# logger_2G_GSM.net
KiCad netlist of a schematic drawn in EAGLE
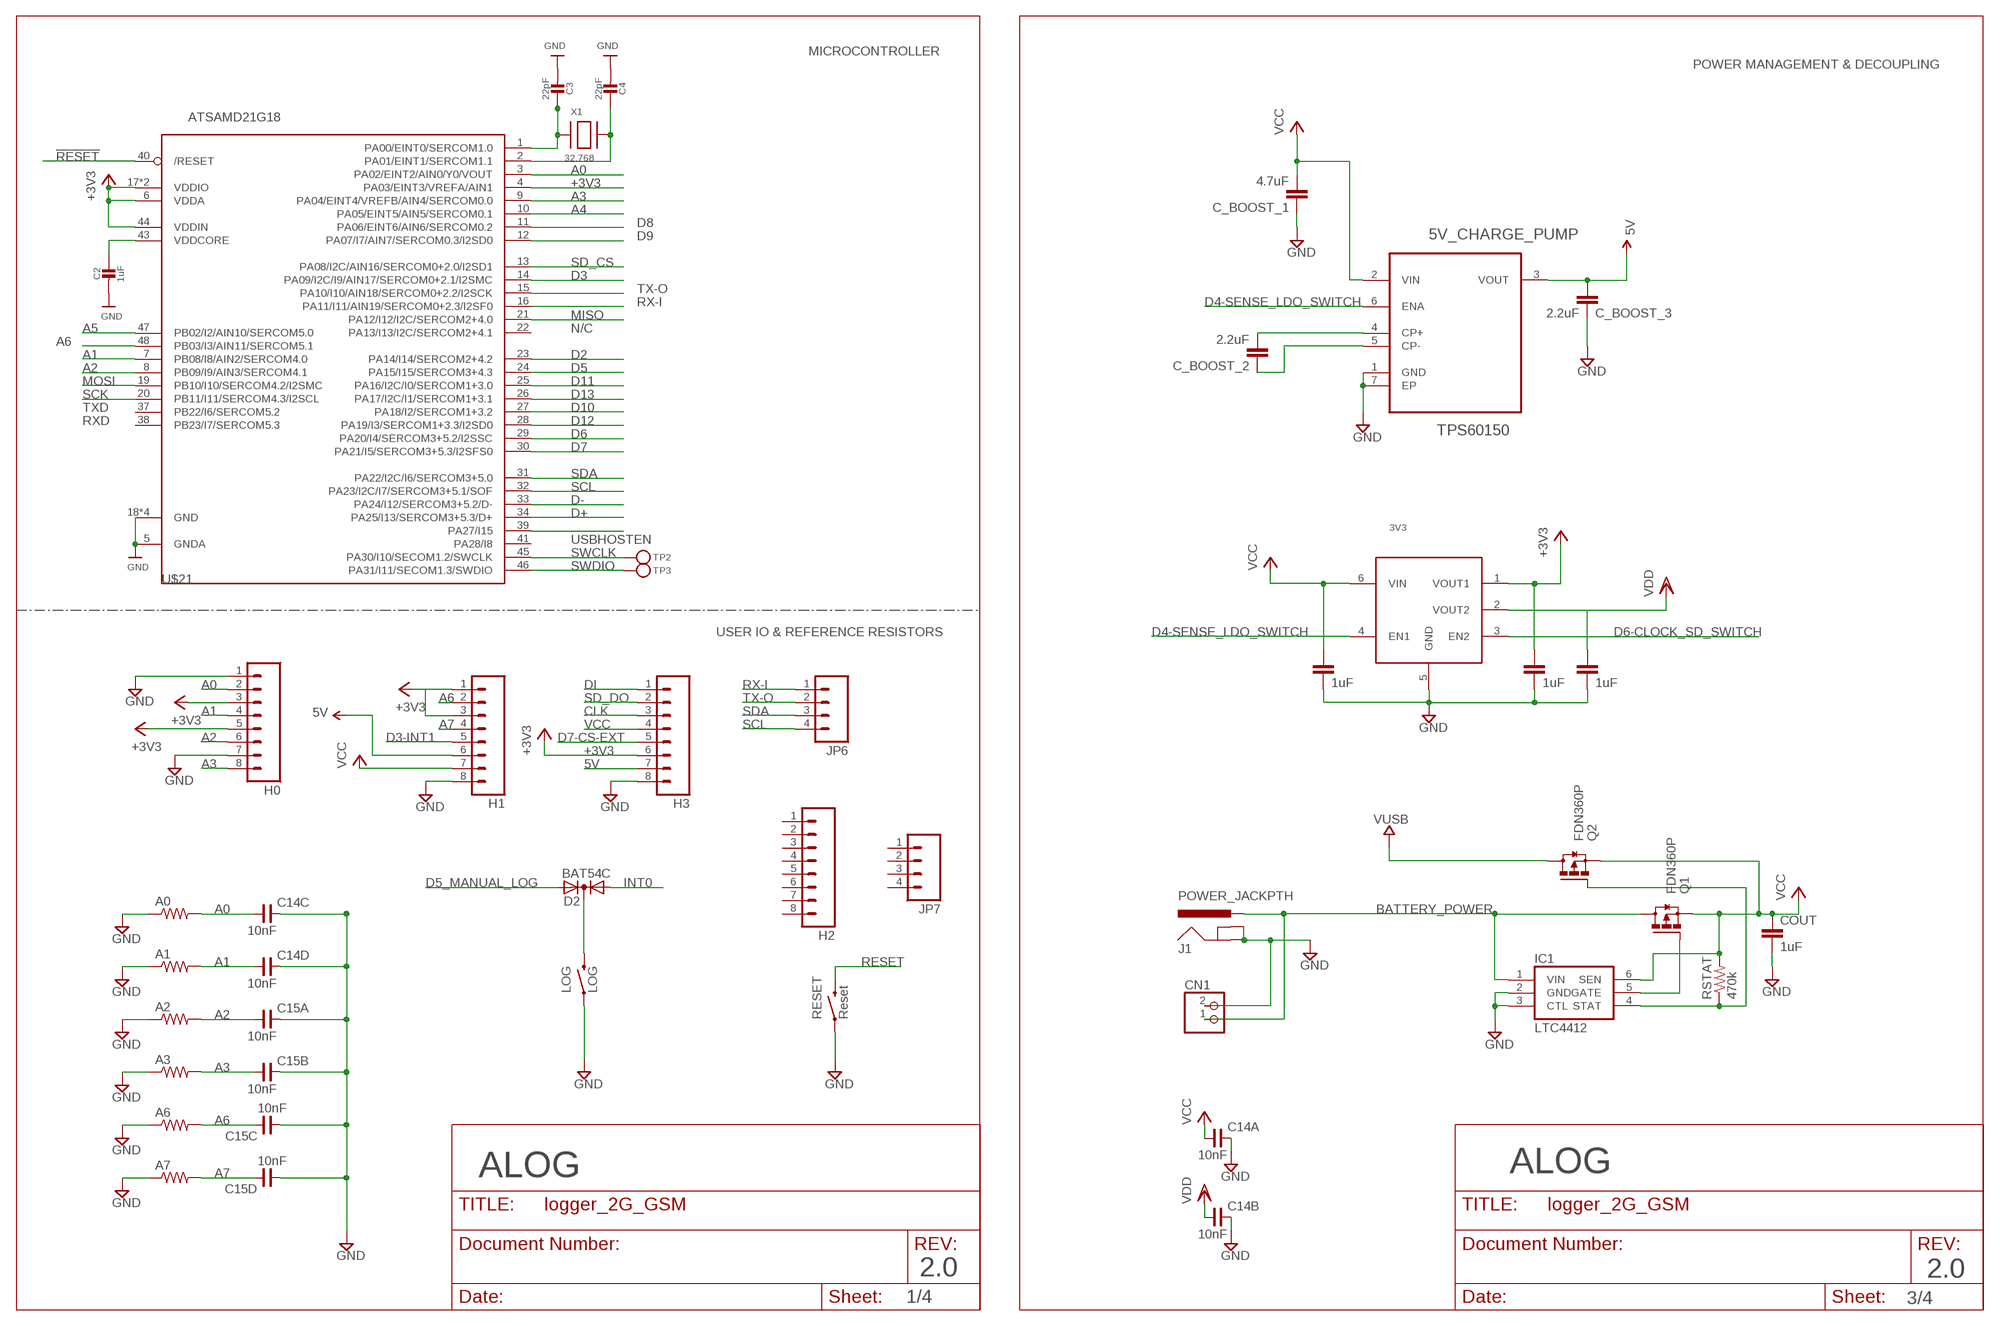
[diagram p0: schematic, sheet 1, part 1 of 2]
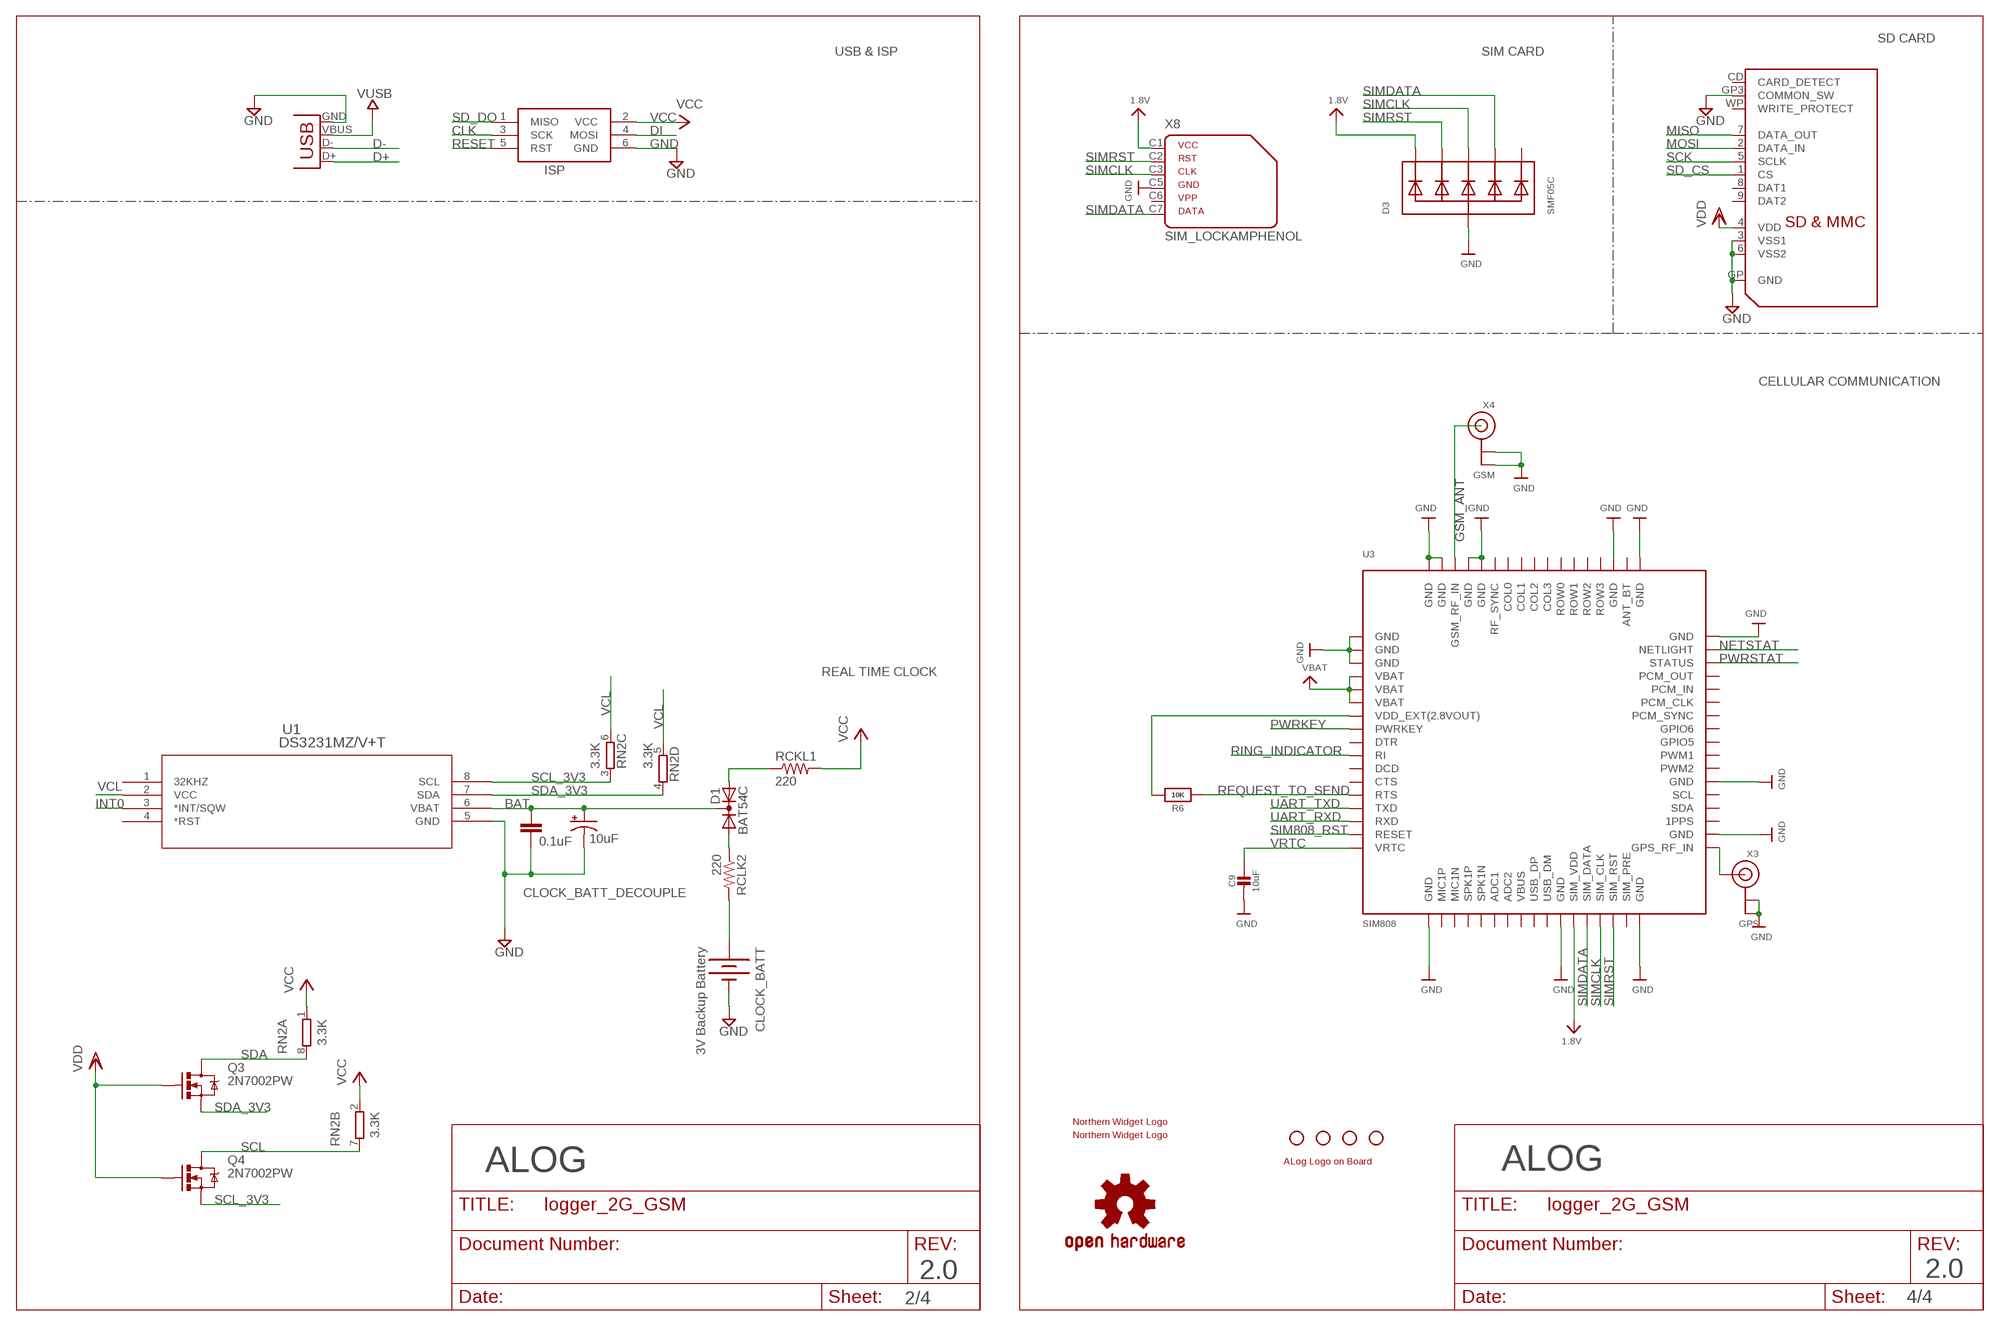
[diagram p1: schematic, sheet 1, part 2 of 2]

(export (version "E")
  (design (tool "Eeschema 10.0.6"))
  (components
    (comp (ref "3V3")
      (value "MIC5380")
      (footprint "eagle-import:6-TMLF")
      (libsource (lib "eagle-import") (part "MIC5380"))
    )
    (comp (ref "5V_CHARGE_PUMP")
      (value "TPS60150")
      (footprint "eagle-import:SON65P200X200X80-7N")
      (fields (field (name "MPN") "TPS60150DRVR"))
      (libsource (lib "eagle-import") (part "TPS60150DRVR"))
    )
    (comp (ref "A0")
      (value "R-US_0207/10")
      (footprint "eagle-import:0207_10")
      (libsource (lib "eagle-import") (part "resistor_R-US_0207/10"))
    )
    (comp (ref "A1")
      (value "R-US_0207/10")
      (footprint "eagle-import:0207_10")
      (libsource (lib "eagle-import") (part "resistor_R-US_0207/10"))
    )
    (comp (ref "A2")
      (value "R-US_0207/10")
      (footprint "eagle-import:0207_10")
      (libsource (lib "eagle-import") (part "resistor_R-US_0207/10"))
    )
    (comp (ref "A3")
      (value "R-US_0207/10")
      (footprint "eagle-import:0207_10")
      (libsource (lib "eagle-import") (part "resistor_R-US_0207/10"))
    )
    (comp (ref "A6")
      (value "R-US_0207/10")
      (footprint "eagle-import:0207_10")
      (libsource (lib "eagle-import") (part "resistor_R-US_0207/10"))
    )
    (comp (ref "A7")
      (value "R-US_0207/10")
      (footprint "eagle-import:0207_10")
      (libsource (lib "eagle-import") (part "resistor_R-US_0207/10"))
    )
    (comp (ref "C2")
      (value "1uF")
      (footprint "eagle-import:0603-NO")
      (libsource (lib "eagle-import") (part "CAP_CERAMIC0603_NO"))
    )
    (comp (ref "C3")
      (value "22pF")
      (footprint "eagle-import:0603-NO")
      (libsource (lib "eagle-import") (part "CAP_CERAMIC0603_NO"))
    )
    (comp (ref "C4")
      (value "22pF")
      (footprint "eagle-import:0603-NO")
      (libsource (lib "eagle-import") (part "CAP_CERAMIC0603_NO"))
    )
    (comp (ref "C9")
      (value "10uF")
      (footprint "eagle-import:0805-NO")
      (libsource (lib "eagle-import") (part "CAP_CERAMIC0805-NOOUTLINE"))
    )
    (comp (ref "C14")
      (value "10nF")
      (footprint "eagle-import:CECJ-1206")
      (libsource (lib "eagle-import") (part "CCA_ECJ-1206"))
    )
    (comp (ref "C15")
      (value "10nF")
      (footprint "eagle-import:CECJ-1206")
      (libsource (lib "eagle-import") (part "CCA_ECJ-1206"))
    )
    (comp (ref "CLOCK_BATT")
      (value "3V Backup Battery")
      (footprint "eagle-import:BATTCON_12MM_PTH")
      (libsource (lib "eagle-import") (part "BATTERY12PTH"))
    )
    (comp (ref "CLOCK_BATT_DECOUP")
      (value "0.1uF")
      (footprint "eagle-import:C0603")
      (libsource (lib "eagle-import") (part "C-EUC0603"))
    )
    (comp (ref "CLOCK_BATT_DECOUPLE")
      (value "10uF")
      (footprint "eagle-import:EIA3216")
      (libsource (lib "eagle-import") (part "CAP_POL1206"))
    )
    (comp (ref "CLOCK_CIN1")
      (value "1uF")
      (footprint "eagle-import:C0603")
      (libsource (lib "eagle-import") (part "C-EUC0603"))
    )
    (comp (ref "CLOCK_CIN2")
      (value "1uF")
      (footprint "eagle-import:C0603")
      (libsource (lib "eagle-import") (part "C-EUC0603"))
    )
    (comp (ref "CLOCK_CIN3")
      (value "1uF")
      (footprint "eagle-import:C0603")
      (libsource (lib "eagle-import") (part "C-EUC0603"))
    )
    (comp (ref "CN1")
      (value "JST_2PIN-THM")
      (footprint "eagle-import:JST-PH-2-THM")
      (libsource (lib "eagle-import") (part "JST_2PIN-THM"))
    )
    (comp (ref "COUT")
      (value "1uF")
      (footprint "eagle-import:C0603")
      (libsource (lib "eagle-import") (part "C-EUC0603"))
    )
    (comp (ref "C_BOOST_1")
      (value "4.7uF")
      (footprint "eagle-import:C0603")
      (libsource (lib "eagle-import") (part "resistor_C-EUC0603"))
    )
    (comp (ref "C_BOOST_2")
      (value "2.2uF")
      (footprint "eagle-import:C0603")
      (libsource (lib "eagle-import") (part "resistor_C-EUC0603"))
    )
    (comp (ref "C_BOOST_3")
      (value "2.2uF")
      (footprint "eagle-import:C0603")
      (libsource (lib "eagle-import") (part "resistor_C-EUC0603"))
    )
    (comp (ref "D1")
      (value "BAT54C")
      (footprint "eagle-import:SOT23C")
      (libsource (lib "eagle-import") (part "DIODE_AC-CA_"))
    )
    (comp (ref "D2")
      (value "BAT54C")
      (footprint "eagle-import:SOT23C")
      (libsource (lib "eagle-import") (part "DIODE_AC-CA_"))
    )
    (comp (ref "D3")
      (value "SMF05C")
      (footprint "eagle-import:SOT363")
      (libsource (lib "eagle-import") (part "TVSARRAY_5LANE"))
    )
    (comp (ref "H0")
      (value "M083.5MM-8")
      (footprint "eagle-import:SCREWTERMINAL-3.5MM-8")
      (libsource (lib "eagle-import") (part "M083.5MM-8"))
    )
    (comp (ref "H1")
      (value "M083.5MM-8")
      (footprint "eagle-import:SCREWTERMINAL-3.5MM-8")
      (libsource (lib "eagle-import") (part "M083.5MM-8"))
    )
    (comp (ref "H2")
      (value "M083.5MM-8")
      (footprint "eagle-import:SCREWTERMINAL-3.5MM-8")
      (libsource (lib "eagle-import") (part "M083.5MM-8"))
    )
    (comp (ref "H3")
      (value "M083.5MM-8")
      (footprint "eagle-import:SCREWTERMINAL-3.5MM-8")
      (libsource (lib "eagle-import") (part "M083.5MM-8"))
    )
    (comp (ref "IC1")
      (value "LTC4412")
      (footprint "eagle-import:TSOT23-6")
      (libsource (lib "eagle-import") (part "LTC4412S6E"))
    )
    (comp (ref "ISP")
      (value "AVRISP-6")
      (footprint "eagle-import:AVRISP")
      (libsource (lib "eagle-import") (part "AVRISP-6"))
    )
    (comp (ref "J1")
      (value "POWER_JACKPTH")
      (footprint "eagle-import:POWER_JACK_PTH")
      (libsource (lib "eagle-import") (part "POWER_JACKPTH"))
    )
    (comp (ref "JP1")
      (value "STAND-OFF")
      (footprint "eagle-import:STAND-OFF")
      (libsource (lib "eagle-import") (part "STAND-OFF"))
    )
    (comp (ref "JP2")
      (value "STAND-OFF")
      (footprint "eagle-import:STAND-OFF")
      (libsource (lib "eagle-import") (part "STAND-OFF"))
    )
    (comp (ref "JP3")
      (value "STAND-OFF")
      (footprint "eagle-import:STAND-OFF")
      (libsource (lib "eagle-import") (part "STAND-OFF"))
    )
    (comp (ref "JP4")
      (value "STAND-OFF")
      (footprint "eagle-import:STAND-OFF")
      (libsource (lib "eagle-import") (part "STAND-OFF"))
    )
    (comp (ref "JP5")
      (value "USB-B")
      (footprint "eagle-import:USB-B-PTH")
      (libsource (lib "eagle-import") (part "USBPTH"))
    )
    (comp (ref "JP6")
      (value "M04SCREW")
      (footprint "eagle-import:SCREWTERMINAL-3.5MM-4")
      (libsource (lib "eagle-import") (part "M04SCREW"))
    )
    (comp (ref "JP7")
      (value "M04SCREW")
      (footprint "eagle-import:SCREWTERMINAL-3.5MM-4")
      (libsource (lib "eagle-import") (part "M04SCREW"))
    )
    (comp (ref "LOG")
      (value "LOG")
      (footprint "eagle-import:TACTILE-PTH")
      (libsource (lib "eagle-import") (part "SWITCH-MOMENTARY-2PTH"))
    )
    (comp (ref "LOGO1")
      (value "OSHW-LOGOM")
      (footprint "eagle-import:OSHW-LOGO-M")
      (libsource (lib "eagle-import") (part "OSHW-LOGOM"))
    )
    (comp (ref "Q1")
      (value "FDN360P")
      (footprint "eagle-import:SUPER-SOT3")
      (libsource (lib "eagle-import") (part "FDN360P"))
    )
    (comp (ref "Q2")
      (value "FDN360P")
      (footprint "eagle-import:SUPER-SOT3")
      (libsource (lib "eagle-import") (part "FDN360P"))
    )
    (comp (ref "Q3")
      (value "2N7002PW")
      (footprint "eagle-import:SOT323")
      (libsource (lib "eagle-import") (part "MOSFET-NCHANNELSOT323"))
    )
    (comp (ref "Q4")
      (value "2N7002PW")
      (footprint "eagle-import:SOT323")
      (libsource (lib "eagle-import") (part "MOSFET-NCHANNELSOT323"))
    )
    (comp (ref "R6")
      (value "10K")
      (footprint "eagle-import:0805-NO")
      (libsource (lib "eagle-import") (part "RESISTOR0805_NOOUTLINE"))
    )
    (comp (ref "RCKL1")
      (value "220")
      (footprint "eagle-import:R0603")
      (libsource (lib "eagle-import") (part "R-US_R0603"))
    )
    (comp (ref "RCLK2")
      (value "220")
      (footprint "eagle-import:R0603")
      (libsource (lib "eagle-import") (part "R-US_R0603"))
    )
    (comp (ref "RESET")
      (value "Reset")
      (footprint "eagle-import:TACTILE-PTH")
      (libsource (lib "eagle-import") (part "SWITCH-MOMENTARY-2PTH"))
    )
    (comp (ref "RN2")
      (value "3.3K")
      (footprint "eagle-import:0603-ARC")
      (libsource (lib "eagle-import") (part "4R-N0603-ARC"))
    )
    (comp (ref "RSTAT")
      (value "470k")
      (footprint "eagle-import:R0603")
      (libsource (lib "eagle-import") (part "R-US_R0603"))
    )
    (comp (ref "SD")
      (value "SDMMC06132")
      (footprint "eagle-import:06132")
      (libsource (lib "eagle-import") (part "SDMMC06132"))
    )
    (comp (ref "TP2")
      (value "TESTPOINTROUND1.5MM")
      (footprint "eagle-import:TESTPOINT_ROUND_1.5MM")
      (libsource (lib "eagle-import") (part "TESTPOINTROUND1.5MM"))
    )
    (comp (ref "TP3")
      (value "TESTPOINTROUND1.5MM")
      (footprint "eagle-import:TESTPOINT_ROUND_1.5MM")
      (libsource (lib "eagle-import") (part "TESTPOINTROUND1.5MM"))
    )
    (comp (ref "U$1")
      (value "NWLOGO")
      (footprint "eagle-import:NWLOGO")
      (libsource (lib "eagle-import") (part "NWLOGO"))
    )
    (comp (ref "U$2")
      (value "ALOG_LOGO_V1_5.5MM")
      (footprint "eagle-import:ALOG_LOGO_V1_SMALL")
      (libsource (lib "eagle-import") (part "ALOG_LOGO_V1_5.5MM"))
    )
    (comp (ref "U$3")
      (value "NWLOGO_MED")
      (footprint "eagle-import:NWLOGO_MED")
      (libsource (lib "eagle-import") (part "NWLOGO_MED"))
    )
    (comp (ref "U$21")
      (value "ATSAMD21G18")
      (footprint "eagle-import:TQFN48_7MM")
      (libsource (lib "eagle-import") (part "ATSAMD21J_QFN"))
    )
    (comp (ref "U1")
      (value "DS3231MZ/V+T")
      (footprint "eagle-import:21-0041B_8")
      (libsource (lib "eagle-import") (part "DS3231MZ/V+T"))
    )
    (comp (ref "U3")
      (value "SIM808")
      (footprint "eagle-import:SIM900_SMT")
      (libsource (lib "eagle-import") (part "GSM_SIM808_LITERAL"))
    )
    (comp (ref "X1")
      (value "32.768")
      (footprint "eagle-import:XTAL3215")
      (libsource (lib "eagle-import") (part "XTAL-3.2X1.5"))
    )
    (comp (ref "X3")
      (value "GPS")
      (footprint "eagle-import:U.FL")
      (libsource (lib "eagle-import") (part "ANTENNA_U.FL"))
    )
    (comp (ref "X4")
      (value "GSM")
      (footprint "eagle-import:U.FL")
      (libsource (lib "eagle-import") (part "ANTENNA_U.FL"))
    )
    (comp (ref "X8")
      (value "SIM_LOCKAMPHENOL")
      (footprint "eagle-import:C707_10M006_512_2")
      (libsource (lib "eagle-import") (part "SIM_LOCKAMPHENOL"))
    )
  )
  (nets
    (net (code "1") (name "+3V3") (class "Default")
      (node (ref "3V3") (pin "1") (pinfunction "VOUT1_1") (pintype "power_in"))
      (node (ref "CLOCK_CIN2") (pin "1") (pinfunction "1_1") (pintype "passive"))
      (node (ref "H0") (pin "3") (pinfunction "3_3") (pintype "passive"))
      (node (ref "H0") (pin "5") (pinfunction "5_5") (pintype "passive"))
      (node (ref "H1") (pin "1") (pinfunction "1_1") (pintype "passive"))
      (node (ref "H1") (pin "3") (pinfunction "3_3") (pintype "passive"))
      (node (ref "H3") (pin "6") (pinfunction "6_6") (pintype "passive"))
      (node (ref "U$21") (pin "17") (pinfunction "VDDIO_17") (pintype "power_in"))
      (node (ref "U$21") (pin "36") (pinfunction "VDDIO_36") (pintype "power_in"))
      (node (ref "U$21") (pin "4") (pinfunction "PA03/EINT3/VREFA/AIN1_4") (pintype "bidirectional"))
      (node (ref "U$21") (pin "44") (pinfunction "VDDIN_44") (pintype "power_in"))
      (node (ref "U$21") (pin "6") (pinfunction "VDDA_6") (pintype "power_in"))
    )
    (net (code "2") (name "/A0") (class "Default")
      (node (ref "A0") (pin "2") (pinfunction "2_2") (pintype "passive"))
      (node (ref "C14") (pin "C1") (pinfunction "1_C1") (pintype "passive"))
      (node (ref "H0") (pin "2") (pinfunction "2_2") (pintype "passive"))
      (node (ref "U$21") (pin "3") (pinfunction "PA02/EINT2/AIN0/Y0/VOUT_3") (pintype "bidirectional"))
    )
    (net (code "3") (name "/A1") (class "Default")
      (node (ref "A1") (pin "2") (pinfunction "2_2") (pintype "passive"))
      (node (ref "C14") (pin "D1") (pinfunction "1_D1") (pintype "passive"))
      (node (ref "H0") (pin "4") (pinfunction "4_4") (pintype "passive"))
      (node (ref "U$21") (pin "7") (pinfunction "PB08/I8/AIN2/SERCOM4.0_7") (pintype "bidirectional"))
    )
    (net (code "4") (name "/A2") (class "Default")
      (node (ref "A2") (pin "2") (pinfunction "2_2") (pintype "passive"))
      (node (ref "C15") (pin "A1") (pinfunction "1_A1") (pintype "passive"))
      (node (ref "H0") (pin "6") (pinfunction "6_6") (pintype "passive"))
      (node (ref "U$21") (pin "8") (pinfunction "PB09/I9/AIN3/SERCOM4.1_8") (pintype "bidirectional"))
    )
    (net (code "5") (name "/A3") (class "Default")
      (node (ref "A3") (pin "2") (pinfunction "2_2") (pintype "passive"))
      (node (ref "C15") (pin "B1") (pinfunction "1_B1") (pintype "passive"))
      (node (ref "H0") (pin "8") (pinfunction "8_8") (pintype "passive"))
      (node (ref "U$21") (pin "9") (pinfunction "PA04/EINT4/VREFB/AIN4/SERCOM0.0_9") (pintype "bidirectional"))
    )
    (net (code "6") (name "/A4") (class "Default")
      (node (ref "U$21") (pin "10") (pinfunction "PA05/EINT5/AIN5/SERCOM0.1_10") (pintype "bidirectional"))
    )
    (net (code "7") (name "/A5") (class "Default")
      (node (ref "U$21") (pin "47") (pinfunction "PB02/I2/AIN10/SERCOM5.0_47") (pintype "bidirectional"))
    )
    (net (code "8") (name "/A6") (class "Default")
      (node (ref "A6") (pin "2") (pinfunction "2_2") (pintype "passive"))
      (node (ref "C15") (pin "C2") (pinfunction "2_C2") (pintype "passive"))
      (node (ref "H1") (pin "2") (pinfunction "2_2") (pintype "passive"))
      (node (ref "U$21") (pin "48") (pinfunction "PB03/I3/AIN11/SERCOM5.1_48") (pintype "bidirectional"))
    )
    (net (code "9") (name "/A7") (class "Default")
      (node (ref "A7") (pin "2") (pinfunction "2_2") (pintype "passive"))
      (node (ref "C15") (pin "D2") (pinfunction "2_D2") (pintype "passive"))
      (node (ref "H1") (pin "4") (pinfunction "4_4") (pintype "passive"))
    )
    (net (code "10") (name "/BAT") (class "Default")
      (node (ref "CLOCK_BATT_DECOUP") (pin "1") (pinfunction "1_1") (pintype "passive"))
      (node (ref "CLOCK_BATT_DECOUPLE") (pin "A") (pinfunction "+_A") (pintype "passive"))
      (node (ref "D1") (pin "3") (pinfunction "K_3") (pintype "passive"))
      (node (ref "U1") (pin "6") (pinfunction "VBAT_6") (pintype "power_in"))
    )
    (net (code "11") (name "/BATTERY_POWER") (class "Default")
      (node (ref "CN1") (pin "1") (pinfunction "2_1") (pintype "passive"))
      (node (ref "IC1") (pin "1") (pinfunction "VIN_1") (pintype "input"))
      (node (ref "J1") (pin "PWR") (pinfunction "PWR_PWR") (pintype "bidirectional"))
      (node (ref "Q1") (pin "3") (pinfunction "D_3") (pintype "passive"))
    )
    (net (code "12") (name "/CLK") (class "Default")
      (node (ref "H3") (pin "3") (pinfunction "3_3") (pintype "passive"))
      (node (ref "ISP") (pin "3") (pinfunction "SCK_3") (pintype "output"))
    )
    (net (code "13") (name "/D+") (class "Default")
      (node (ref "JP5") (pin "D+") (pinfunction "D+_D+") (pintype "bidirectional"))
      (node (ref "U$21") (pin "34") (pinfunction "PA25/I13/SERCOM3+5.3/D+_34") (pintype "bidirectional"))
    )
    (net (code "14") (name "/D-") (class "Default")
      (node (ref "JP5") (pin "D-") (pinfunction "D-_D-") (pintype "bidirectional"))
      (node (ref "U$21") (pin "33") (pinfunction "PA24/I12/SERCOM3+5.2/D-_33") (pintype "bidirectional"))
    )
    (net (code "15") (name "/D2") (class "Default")
      (node (ref "U$21") (pin "23") (pinfunction "PA14/I14/SERCOM2+4.2_23") (pintype "bidirectional"))
    )
    (net (code "16") (name "/D3") (class "Default")
      (node (ref "U$21") (pin "14") (pinfunction "PA09/I2C/I9/AIN17/SERCOM0+2.1/I2SMC_14") (pintype "bidirectional"))
    )
    (net (code "17") (name "/D3-INT1") (class "Default")
      (node (ref "H1") (pin "5") (pinfunction "5_5") (pintype "passive"))
    )
    (net (code "18") (name "/D4-SENSE_LDO_SWITCH") (class "Default")
      (node (ref "3V3") (pin "4") (pinfunction "EN1_4") (pintype "input"))
      (node (ref "5V_CHARGE_PUMP") (pin "6") (pinfunction "ENA_6") (pintype "input"))
    )
    (net (code "19") (name "/D5") (class "Default")
      (node (ref "U$21") (pin "24") (pinfunction "PA15/I15/SERCOM3+4.3_24") (pintype "bidirectional"))
    )
    (net (code "20") (name "/D5_MANUAL_LOG") (class "Default")
      (node (ref "D2") (pin "2") (pinfunction "A2_2") (pintype "passive"))
    )
    (net (code "21") (name "/D6") (class "Default")
      (node (ref "U$21") (pin "29") (pinfunction "PA20/I4/SERCOM3+5.2/I2SSC_29") (pintype "bidirectional"))
    )
    (net (code "22") (name "/D6-CLOCK_SD_SWITCH") (class "Default")
      (node (ref "3V3") (pin "3") (pinfunction "EN2_3") (pintype "input"))
    )
    (net (code "23") (name "/D7") (class "Default")
      (node (ref "U$21") (pin "30") (pinfunction "PA21/I5/SERCOM3+5.3/I2SFS0_30") (pintype "bidirectional"))
    )
    (net (code "24") (name "/D7-CS-EXT") (class "Default")
      (node (ref "H3") (pin "5") (pinfunction "5_5") (pintype "passive"))
    )
    (net (code "25") (name "/D8") (class "Default")
      (node (ref "U$21") (pin "11") (pinfunction "PA06/EINT6/AIN6/SERCOM0.2_11") (pintype "bidirectional"))
    )
    (net (code "26") (name "/D9") (class "Default")
      (node (ref "U$21") (pin "12") (pinfunction "PA07/I7/AIN7/SERCOM0.3/I2SD0_12") (pintype "bidirectional"))
    )
    (net (code "27") (name "/D10") (class "Default")
      (node (ref "U$21") (pin "27") (pinfunction "PA18/I2/SERCOM1+3.2_27") (pintype "bidirectional"))
    )
    (net (code "28") (name "/D11") (class "Default")
      (node (ref "U$21") (pin "25") (pinfunction "PA16/I2C/I0/SERCOM1+3.0_25") (pintype "bidirectional"))
    )
    (net (code "29") (name "/D12") (class "Default")
      (node (ref "U$21") (pin "28") (pinfunction "PA19/I3/SERCOM1+3.3/I2SD0_28") (pintype "bidirectional"))
    )
    (net (code "30") (name "/D13") (class "Default")
      (node (ref "U$21") (pin "26") (pinfunction "PA17/I2C/I1/SERCOM1+3.1_26") (pintype "bidirectional"))
    )
    (net (code "31") (name "/DI") (class "Default")
      (node (ref "H3") (pin "1") (pinfunction "1_1") (pintype "passive"))
      (node (ref "ISP") (pin "4") (pinfunction "MOSI_4") (pintype "output"))
    )
    (net (code "32") (name "/GSM_ANT") (class "Default")
      (node (ref "U3") (pin "P$66") (pinfunction "GSM_RF_IN_P$66") (pintype "input"))
      (node (ref "X4") (pin "3") (pinfunction "SIGNAL_3") (pintype "passive"))
    )
    (net (code "33") (name "/INT0") (class "Default")
      (node (ref "D2") (pin "1") (pinfunction "A1_1") (pintype "passive"))
      (node (ref "U1") (pin "3") (pinfunction "*INT/SQW_3") (pintype "passive"))
    )
    (net (code "34") (name "/MISO") (class "Default")
      (node (ref "SD") (pin "7") (pinfunction "DATA_OUT_7") (pintype "output"))
      (node (ref "U$21") (pin "21") (pinfunction "PA12/I12/I2C/SERCOM2+4.0_21") (pintype "bidirectional"))
    )
    (net (code "35") (name "/MOSI") (class "Default")
      (node (ref "SD") (pin "2") (pinfunction "DATA_IN_2") (pintype "input"))
      (node (ref "U$21") (pin "19") (pinfunction "PB10/I10/SERCOM4.2/I2SMC_19") (pintype "bidirectional"))
    )
    (net (code "36") (name "/NETSTAT") (class "Default")
      (node (ref "U3") (pin "P$50") (pinfunction "NETLIGHT_P$50") (pintype "output"))
    )
    (net (code "37") (name "/PWRKEY") (class "Default")
      (node (ref "U3") (pin "P$8") (pinfunction "PWRKEY_P$8") (pintype "input"))
    )
    (net (code "38") (name "/PWRSTAT") (class "Default")
      (node (ref "U3") (pin "P$49") (pinfunction "STATUS_P$49") (pintype "output"))
    )
    (net (code "39") (name "/REQUEST_TO_SEND") (class "Default")
      (node (ref "R6") (pin "1") (pinfunction "1_1") (pintype "passive"))
      (node (ref "U3") (pin "P$13") (pinfunction "RTS_P$13") (pintype "input"))
    )
    (net (code "40") (name "/RESET") (class "Default")
      (node (ref "ISP") (pin "5") (pinfunction "RST_5") (pintype "output"))
      (node (ref "RESET") (pin "3") (pinfunction "2_3") (pintype "passive"))
    )
    (net (code "41") (name "/RING_INDICATOR") (class "Default")
      (node (ref "U3") (pin "P$10") (pinfunction "RI_P$10") (pintype "output"))
    )
    (net (code "42") (name "/RX-I") (class "Default")
      (node (ref "JP6") (pin "1") (pinfunction "1_1") (pintype "passive"))
      (node (ref "U$21") (pin "16") (pinfunction "PA11/I11/AIN19/SERCOM0+2.3/I2SF0_16") (pintype "bidirectional"))
    )
    (net (code "43") (name "/SCK") (class "Default")
      (node (ref "SD") (pin "5") (pinfunction "SCLK_5") (pintype "input"))
      (node (ref "U$21") (pin "20") (pinfunction "PB11/I11/SERCOM4.3/I2SCL_20") (pintype "bidirectional"))
    )
    (net (code "44") (name "/SCL") (class "Default")
      (node (ref "JP6") (pin "4") (pinfunction "4_4") (pintype "passive"))
      (node (ref "Q4") (pin "3") (pinfunction "D_3") (pintype "passive"))
      (node (ref "RN2") (pin "7") (pinfunction "2_7") (pintype "passive"))
      (node (ref "U$21") (pin "32") (pinfunction "PA23/I2C/I7/SERCOM3+5.1/SOF_32") (pintype "bidirectional"))
    )
    (net (code "45") (name "/SCL_3V3") (class "Default")
      (node (ref "Q4") (pin "2") (pinfunction "S_2") (pintype "passive"))
      (node (ref "RN2") (pin "3") (pinfunction "1_3") (pintype "passive"))
      (node (ref "U1") (pin "8") (pinfunction "SCL_8") (pintype "passive"))
    )
    (net (code "46") (name "/SDA") (class "Default")
      (node (ref "JP6") (pin "3") (pinfunction "3_3") (pintype "passive"))
      (node (ref "Q3") (pin "3") (pinfunction "D_3") (pintype "passive"))
      (node (ref "RN2") (pin "8") (pinfunction "2_8") (pintype "passive"))
      (node (ref "U$21") (pin "31") (pinfunction "PA22/I2C/I6/SERCOM3+5.0_31") (pintype "bidirectional"))
    )
    (net (code "47") (name "/SDA_3V3") (class "Default")
      (node (ref "Q3") (pin "2") (pinfunction "S_2") (pintype "passive"))
      (node (ref "RN2") (pin "4") (pinfunction "1_4") (pintype "passive"))
      (node (ref "U1") (pin "7") (pinfunction "SDA_7") (pintype "passive"))
    )
    (net (code "48") (name "/SD_CS") (class "Default")
      (node (ref "SD") (pin "1") (pinfunction "CS_1") (pintype "input"))
      (node (ref "U$21") (pin "13") (pinfunction "PA08/I2C/AIN16/SERCOM0+2.0/I2SD1_13") (pintype "bidirectional"))
    )
    (net (code "49") (name "/SD_DO") (class "Default")
      (node (ref "H3") (pin "2") (pinfunction "2_2") (pintype "passive"))
      (node (ref "ISP") (pin "1") (pinfunction "MISO_1") (pintype "input"))
    )
    (net (code "50") (name "/SIM808_RST") (class "Default")
      (node (ref "U3") (pin "P$16") (pinfunction "RESET_P$16") (pintype "input"))
    )
    (net (code "51") (name "/SIMCLK") (class "Default")
      (node (ref "D3") (pin "4") (pinfunction "C3_4") (pintype "passive"))
      (node (ref "U3") (pin "P$31") (pinfunction "SIM_CLK_P$31") (pintype "output"))
      (node (ref "X8") (pin "C3") (pinfunction "3_C3") (pintype "passive"))
    )
    (net (code "52") (name "/SIMDATA") (class "Default")
      (node (ref "D3") (pin "5") (pinfunction "C4_5") (pintype "passive"))
      (node (ref "U3") (pin "P$30") (pinfunction "SIM_DATA_P$30") (pintype "bidirectional"))
      (node (ref "X8") (pin "C7") (pinfunction "6_C7") (pintype "passive"))
    )
    (net (code "53") (name "/SIMRST") (class "Default")
      (node (ref "D3") (pin "3") (pinfunction "C2_3") (pintype "passive"))
      (node (ref "U3") (pin "P$32") (pinfunction "SIM_RST_P$32") (pintype "output"))
      (node (ref "X8") (pin "C2") (pinfunction "2_C2") (pintype "passive"))
    )
    (net (code "54") (name "/SWCLK") (class "Default")
      (node (ref "TP2") (pin "P$1") (pinfunction "P$1_P$1") (pintype "bidirectional"))
      (node (ref "U$21") (pin "45") (pinfunction "PA30/I10/SECOM1.2/SWCLK_45") (pintype "bidirectional"))
    )
    (net (code "55") (name "/SWDIO") (class "Default")
      (node (ref "TP3") (pin "P$1") (pinfunction "P$1_P$1") (pintype "bidirectional"))
      (node (ref "U$21") (pin "46") (pinfunction "PA31/I11/SECOM1.3/SWDIO_46") (pintype "bidirectional"))
    )
    (net (code "56") (name "/TX-O") (class "Default")
      (node (ref "JP6") (pin "2") (pinfunction "2_2") (pintype "passive"))
      (node (ref "U$21") (pin "15") (pinfunction "PA10/I10/AIN18/SERCOM0+2.2/I2SCK_15") (pintype "bidirectional"))
    )
    (net (code "57") (name "/UART_RXD") (class "Default")
      (node (ref "U3") (pin "P$15") (pinfunction "RXD_P$15") (pintype "input"))
    )
    (net (code "58") (name "/UART_TXD") (class "Default")
      (node (ref "U3") (pin "P$14") (pinfunction "TXD_P$14") (pintype "output"))
    )
    (net (code "59") (name "/VBUS") (class "Default")
      (node (ref "U3") (pin "P$25") (pinfunction "VBUS_P$25") (pintype "power_in"))
    )
    (net (code "60") (name "/VCL") (class "Default")
      (node (ref "RN2") (pin "5") (pinfunction "2_5") (pintype "passive"))
      (node (ref "RN2") (pin "6") (pinfunction "2_6") (pintype "passive"))
      (node (ref "U1") (pin "2") (pinfunction "VCC_2") (pintype "power_in"))
    )
    (net (code "61") (name "/VRTC") (class "Default")
      (node (ref "C9") (pin "1") (pinfunction "1_1") (pintype "passive"))
      (node (ref "U3") (pin "P$17") (pinfunction "VRTC_P$17") (pintype "power_in"))
    )
    (net (code "62") (name "/~{RESET}") (class "Default")
      (node (ref "U$21") (pin "40") (pinfunction "/RESET_40") (pintype "bidirectional"))
    )
    (net (code "63") (name "1.8V") (class "Default")
      (node (ref "D3") (pin "1") (pinfunction "C1_1") (pintype "passive"))
      (node (ref "U3") (pin "P$29") (pinfunction "SIM_VDD_P$29") (pintype "power_in"))
      (node (ref "X8") (pin "C1") (pinfunction "1_C1") (pintype "passive"))
    )
    (net (code "64") (name "5V") (class "Default")
      (node (ref "5V_CHARGE_PUMP") (pin "3") (pinfunction "VOUT_3") (pintype "output"))
      (node (ref "C_BOOST_3") (pin "2") (pinfunction "2_2") (pintype "passive"))
      (node (ref "H1") (pin "6") (pinfunction "6_6") (pintype "passive"))
      (node (ref "H3") (pin "7") (pinfunction "7_7") (pintype "passive"))
    )
    (net (code "65") (name "GND") (class "Default")
      (node (ref "3V3") (pin "5") (pinfunction "GND_5") (pintype "power_in"))
      (node (ref "5V_CHARGE_PUMP") (pin "1") (pinfunction "GND_1") (pintype "passive"))
      (node (ref "5V_CHARGE_PUMP") (pin "7") (pinfunction "EP_7") (pintype "passive"))
      (node (ref "A0") (pin "1") (pinfunction "1_1") (pintype "passive"))
      (node (ref "A1") (pin "1") (pinfunction "1_1") (pintype "passive"))
      (node (ref "A2") (pin "1") (pinfunction "1_1") (pintype "passive"))
      (node (ref "A3") (pin "1") (pinfunction "1_1") (pintype "passive"))
      (node (ref "A6") (pin "1") (pinfunction "1_1") (pintype "passive"))
      (node (ref "A7") (pin "1") (pinfunction "1_1") (pintype "passive"))
      (node (ref "C14") (pin "A2") (pinfunction "2_A2") (pintype "passive"))
      (node (ref "C14") (pin "B2") (pinfunction "2_B2") (pintype "passive"))
      (node (ref "C14") (pin "C2") (pinfunction "2_C2") (pintype "passive"))
      (node (ref "C14") (pin "D2") (pinfunction "2_D2") (pintype "passive"))
      (node (ref "C15") (pin "A2") (pinfunction "2_A2") (pintype "passive"))
      (node (ref "C15") (pin "B2") (pinfunction "2_B2") (pintype "passive"))
      (node (ref "C15") (pin "C1") (pinfunction "1_C1") (pintype "passive"))
      (node (ref "C15") (pin "D1") (pinfunction "1_D1") (pintype "passive"))
      (node (ref "C2") (pin "2") (pinfunction "2_2") (pintype "passive"))
      (node (ref "C3") (pin "2") (pinfunction "2_2") (pintype "passive"))
      (node (ref "C4") (pin "2") (pinfunction "2_2") (pintype "passive"))
      (node (ref "C9") (pin "2") (pinfunction "2_2") (pintype "passive"))
      (node (ref "CLOCK_BATT") (pin "GND") (pinfunction "-_GND") (pintype "power_in"))
      (node (ref "CLOCK_BATT_DECOUP") (pin "2") (pinfunction "2_2") (pintype "passive"))
      (node (ref "CLOCK_BATT_DECOUPLE") (pin "C") (pinfunction "-_C") (pintype "passive"))
      (node (ref "CLOCK_CIN1") (pin "2") (pinfunction "2_2") (pintype "passive"))
      (node (ref "CLOCK_CIN2") (pin "2") (pinfunction "2_2") (pintype "passive"))
      (node (ref "CLOCK_CIN3") (pin "2") (pinfunction "2_2") (pintype "passive"))
      (node (ref "CN1") (pin "2") (pinfunction "1_2") (pintype "passive"))
      (node (ref "COUT") (pin "2") (pinfunction "2_2") (pintype "passive"))
      (node (ref "C_BOOST_1") (pin "1") (pinfunction "1_1") (pintype "passive"))
      (node (ref "C_BOOST_3") (pin "1") (pinfunction "1_1") (pintype "passive"))
      (node (ref "D3") (pin "2") (pinfunction "A_2") (pintype "passive"))
      (node (ref "H0") (pin "1") (pinfunction "1_1") (pintype "passive"))
      (node (ref "H0") (pin "7") (pinfunction "7_7") (pintype "passive"))
      (node (ref "H1") (pin "8") (pinfunction "8_8") (pintype "passive"))
      (node (ref "H3") (pin "8") (pinfunction "8_8") (pintype "passive"))
      (node (ref "IC1") (pin "2") (pinfunction "GND_2") (pintype "passive"))
      (node (ref "IC1") (pin "3") (pinfunction "CTL_3") (pintype "input"))
      (node (ref "ISP") (pin "6") (pinfunction "GND_6") (pintype "power_in"))
      (node (ref "J1") (pin "GND") (pinfunction "GND_GND") (pintype "bidirectional"))
      (node (ref "J1") (pin "GNDBREAK") (pinfunction "GNDBREAK_GNDBREAK") (pintype "bidirectional"))
      (node (ref "JP5") (pin "GND") (pinfunction "GND_GND") (pintype "bidirectional"))
      (node (ref "LOG") (pin "1") (pinfunction "1_1") (pintype "passive"))
      (node (ref "RESET") (pin "1") (pinfunction "1_1") (pintype "passive"))
      (node (ref "SD") (pin "3") (pinfunction "VSS1_3") (pintype "power_in"))
      (node (ref "SD") (pin "6") (pinfunction "VSS2_6") (pintype "power_in"))
      (node (ref "SD") (pin "GP") (pinfunction "GND_GP") (pintype "power_in"))
      (node (ref "SD") (pin "GP3") (pinfunction "COMMON_SW_GP3") (pintype "passive"))
      (node (ref "U$21") (pin "18") (pinfunction "GND_18") (pintype "power_in"))
      (node (ref "U$21") (pin "35") (pinfunction "GND_35") (pintype "power_in"))
      (node (ref "U$21") (pin "42") (pinfunction "GND_42") (pintype "power_in"))
      (node (ref "U$21") (pin "5") (pinfunction "GNDA_5") (pintype "power_in"))
      (node (ref "U$21") (pin "THERMAL") (pinfunction "GND_THERMAL") (pintype "power_in"))
      (node (ref "U1") (pin "5") (pinfunction "GND_5") (pintype "power_in"))
      (node (ref "U3") (pin "P$1") (pinfunction "GND_P$1") (pintype "power_in"))
      (node (ref "U3") (pin "P$18") (pinfunction "GND_P$18") (pintype "power_in"))
      (node (ref "U3") (pin "P$2") (pinfunction "GND_P$2") (pintype "power_in"))
      (node (ref "U3") (pin "P$28") (pinfunction "GND_P$28") (pintype "power_in"))
      (node (ref "U3") (pin "P$3") (pinfunction "GND_P$3") (pintype "power_in"))
      (node (ref "U3") (pin "P$34") (pinfunction "GND_P$34") (pintype "power_in"))
      (node (ref "U3") (pin "P$36") (pinfunction "GND_P$36") (pintype "power_in"))
      (node (ref "U3") (pin "P$40") (pinfunction "GND_P$40") (pintype "power_in"))
      (node (ref "U3") (pin "P$51") (pinfunction "GND_P$51") (pintype "power_in"))
      (node (ref "U3") (pin "P$52") (pinfunction "GND_P$52") (pintype "power_in"))
      (node (ref "U3") (pin "P$54") (pinfunction "GND_P$54") (pintype "power_in"))
      (node (ref "U3") (pin "P$64") (pinfunction "GND_P$64") (pintype "power_in"))
      (node (ref "U3") (pin "P$65") (pinfunction "GND_P$65") (pintype "power_in"))
      (node (ref "U3") (pin "P$67") (pinfunction "GND_P$67") (pintype "power_in"))
      (node (ref "U3") (pin "P$68") (pinfunction "GND_P$68") (pintype "power_in"))
      (node (ref "X3") (pin "1") (pinfunction "GND_1") (pintype "passive"))
      (node (ref "X3") (pin "2") (pinfunction "GND_2") (pintype "passive"))
      (node (ref "X4") (pin "1") (pinfunction "GND_1") (pintype "passive"))
      (node (ref "X4") (pin "2") (pinfunction "GND_2") (pintype "passive"))
      (node (ref "X8") (pin "C5") (pinfunction "4_C5") (pintype "passive"))
    )
    (net (code "66") (name "Net-(5V_CHARGE_PUMP-CP+)") (class "Default")
      (node (ref "5V_CHARGE_PUMP") (pin "4") (pinfunction "CP+_4") (pintype "passive"))
      (node (ref "C_BOOST_2") (pin "2") (pinfunction "2_2") (pintype "passive"))
    )
    (net (code "67") (name "Net-(5V_CHARGE_PUMP-CP-)") (class "Default")
      (node (ref "5V_CHARGE_PUMP") (pin "5") (pinfunction "CP-_5") (pintype "passive"))
      (node (ref "C_BOOST_2") (pin "1") (pinfunction "1_1") (pintype "passive"))
    )
    (net (code "68") (name "Net-(CLOCK_BATT-+)") (class "Default")
      (node (ref "CLOCK_BATT") (pin "VCC@1") (pinfunction "+_VCC@1") (pintype "power_in"))
      (node (ref "RCLK2") (pin "2") (pinfunction "2_2") (pintype "passive"))
    )
    (net (code "69") (name "Net-(D1-A1)") (class "Default")
      (node (ref "D1") (pin "1") (pinfunction "A1_1") (pintype "passive"))
      (node (ref "RCLK2") (pin "1") (pinfunction "1_1") (pintype "passive"))
    )
    (net (code "70") (name "Net-(D1-A2)") (class "Default")
      (node (ref "D1") (pin "2") (pinfunction "A2_2") (pintype "passive"))
      (node (ref "RCKL1") (pin "1") (pinfunction "1_1") (pintype "passive"))
    )
    (net (code "71") (name "Net-(D2-K)") (class "Default")
      (node (ref "D2") (pin "3") (pinfunction "K_3") (pintype "passive"))
      (node (ref "LOG") (pin "3") (pinfunction "2_3") (pintype "passive"))
    )
    (net (code "72") (name "Net-(IC1-GATE)") (class "Default")
      (node (ref "IC1") (pin "5") (pinfunction "GATE_5") (pintype "output"))
      (node (ref "Q1") (pin "1") (pinfunction "G_1") (pintype "passive"))
    )
    (net (code "73") (name "Net-(IC1-STAT)") (class "Default")
      (node (ref "IC1") (pin "4") (pinfunction "STAT_4") (pintype "open_collector"))
      (node (ref "Q2") (pin "1") (pinfunction "G_1") (pintype "passive"))
      (node (ref "RSTAT") (pin "1") (pinfunction "1_1") (pintype "passive"))
    )
    (net (code "74") (name "Net-(U$21-PA00{slash}EINT0{slash}SERCOM1.0)") (class "Default")
      (node (ref "C3") (pin "1") (pinfunction "1_1") (pintype "passive"))
      (node (ref "U$21") (pin "1") (pinfunction "PA00/EINT0/SERCOM1.0_1") (pintype "bidirectional"))
      (node (ref "X1") (pin "P$1") (pinfunction "P$1_P$1") (pintype "bidirectional"))
    )
    (net (code "75") (name "Net-(U$21-PA01{slash}EINT1{slash}SERCOM1.1)") (class "Default")
      (node (ref "C4") (pin "1") (pinfunction "1_1") (pintype "passive"))
      (node (ref "U$21") (pin "2") (pinfunction "PA01/EINT1/SERCOM1.1_2") (pintype "bidirectional"))
      (node (ref "X1") (pin "P$2") (pinfunction "P$2_P$2") (pintype "bidirectional"))
    )
    (net (code "76") (name "Net-(U$21-VDDCORE)") (class "Default")
      (node (ref "C2") (pin "1") (pinfunction "1_1") (pintype "passive"))
      (node (ref "U$21") (pin "43") (pinfunction "VDDCORE_43") (pintype "power_in"))
    )
    (net (code "77") (name "Net-(U3-GPS_RF_IN)") (class "Default")
      (node (ref "U3") (pin "P$35") (pinfunction "GPS_RF_IN_P$35") (pintype "bidirectional"))
      (node (ref "X3") (pin "3") (pinfunction "SIGNAL_3") (pintype "passive"))
    )
    (net (code "78") (name "Net-(U3-VDD_EXT(2.8VOUT))") (class "Default")
      (node (ref "R6") (pin "2") (pinfunction "2_2") (pintype "passive"))
      (node (ref "U3") (pin "P$7") (pinfunction "VDD_EXT(2.8VOUT)_P$7") (pintype "power_in"))
    )
    (net (code "79") (name "VBAT") (class "Default")
      (node (ref "U3") (pin "P$4") (pinfunction "VBAT_P$4") (pintype "power_in"))
      (node (ref "U3") (pin "P$5") (pinfunction "VBAT_P$5") (pintype "power_in"))
      (node (ref "U3") (pin "P$6") (pinfunction "VBAT_P$6") (pintype "power_in"))
    )
    (net (code "80") (name "VCC") (class "Default")
      (node (ref "3V3") (pin "6") (pinfunction "VIN_6") (pintype "power_in"))
      (node (ref "5V_CHARGE_PUMP") (pin "2") (pinfunction "VIN_2") (pintype "power_in"))
      (node (ref "C14") (pin "A1") (pinfunction "1_A1") (pintype "passive"))
      (node (ref "CLOCK_CIN1") (pin "1") (pinfunction "1_1") (pintype "passive"))
      (node (ref "COUT") (pin "1") (pinfunction "1_1") (pintype "passive"))
      (node (ref "C_BOOST_1") (pin "2") (pinfunction "2_2") (pintype "passive"))
      (node (ref "H1") (pin "7") (pinfunction "7_7") (pintype "passive"))
      (node (ref "H3") (pin "4") (pinfunction "4_4") (pintype "passive"))
      (node (ref "IC1") (pin "6") (pinfunction "SEN_6") (pintype "input"))
      (node (ref "ISP") (pin "2") (pinfunction "VCC_2") (pintype "power_in"))
      (node (ref "Q1") (pin "2") (pinfunction "S_2") (pintype "passive"))
      (node (ref "Q2") (pin "2") (pinfunction "S_2") (pintype "passive"))
      (node (ref "RCKL1") (pin "2") (pinfunction "2_2") (pintype "passive"))
      (node (ref "RN2") (pin "1") (pinfunction "1_1") (pintype "passive"))
      (node (ref "RN2") (pin "2") (pinfunction "1_2") (pintype "passive"))
      (node (ref "RSTAT") (pin "2") (pinfunction "2_2") (pintype "passive"))
    )
    (net (code "81") (name "VDD") (class "Default")
      (node (ref "3V3") (pin "2") (pinfunction "VOUT2_2") (pintype "power_in"))
      (node (ref "C14") (pin "B1") (pinfunction "1_B1") (pintype "passive"))
      (node (ref "CLOCK_CIN3") (pin "1") (pinfunction "1_1") (pintype "passive"))
      (node (ref "Q3") (pin "1") (pinfunction "G_1") (pintype "passive"))
      (node (ref "Q4") (pin "1") (pinfunction "G_1") (pintype "passive"))
      (node (ref "SD") (pin "4") (pinfunction "VDD_4") (pintype "power_in"))
    )
    (net (code "82") (name "VUSB") (class "Default")
      (node (ref "JP5") (pin "VBUS") (pinfunction "VBUS_VBUS") (pintype "bidirectional"))
      (node (ref "Q2") (pin "3") (pinfunction "D_3") (pintype "passive"))
    )
    (net (code "83") (name "unconnected-(D3-C5-Pad6)") (class "Default")
      (node (ref "D3") (pin "6") (pinfunction "C5_6") (pintype "passive"))
    )
    (net (code "84") (name "unconnected-(H2-Pad1)") (class "Default")
      (node (ref "H2") (pin "1") (pinfunction "1_1") (pintype "passive"))
    )
    (net (code "85") (name "unconnected-(H2-Pad2)") (class "Default")
      (node (ref "H2") (pin "2") (pinfunction "2_2") (pintype "passive"))
    )
    (net (code "86") (name "unconnected-(H2-Pad3)") (class "Default")
      (node (ref "H2") (pin "3") (pinfunction "3_3") (pintype "passive"))
    )
    (net (code "87") (name "unconnected-(H2-Pad4)") (class "Default")
      (node (ref "H2") (pin "4") (pinfunction "4_4") (pintype "passive"))
    )
    (net (code "88") (name "unconnected-(H2-Pad5)") (class "Default")
      (node (ref "H2") (pin "5") (pinfunction "5_5") (pintype "passive"))
    )
    (net (code "89") (name "unconnected-(H2-Pad6)") (class "Default")
      (node (ref "H2") (pin "6") (pinfunction "6_6") (pintype "passive"))
    )
    (net (code "90") (name "unconnected-(H2-Pad7)") (class "Default")
      (node (ref "H2") (pin "7") (pinfunction "7_7") (pintype "passive"))
    )
    (net (code "91") (name "unconnected-(H2-Pad8)") (class "Default")
      (node (ref "H2") (pin "8") (pinfunction "8_8") (pintype "passive"))
    )
    (net (code "92") (name "unconnected-(JP7-Pad1)") (class "Default")
      (node (ref "JP7") (pin "1") (pinfunction "1_1") (pintype "passive"))
    )
    (net (code "93") (name "unconnected-(JP7-Pad2)") (class "Default")
      (node (ref "JP7") (pin "2") (pinfunction "2_2") (pintype "passive"))
    )
    (net (code "94") (name "unconnected-(JP7-Pad3)") (class "Default")
      (node (ref "JP7") (pin "3") (pinfunction "3_3") (pintype "passive"))
    )
    (net (code "95") (name "unconnected-(JP7-Pad4)") (class "Default")
      (node (ref "JP7") (pin "4") (pinfunction "4_4") (pintype "passive"))
    )
    (net (code "96") (name "unconnected-(SD-CARD_DETECT-PadCD)") (class "Default")
      (node (ref "SD") (pin "CD") (pinfunction "CARD_DETECT_CD") (pintype "passive"))
    )
    (net (code "97") (name "unconnected-(SD-DAT1-Pad8)") (class "Default")
      (node (ref "SD") (pin "8") (pinfunction "DAT1_8") (pintype "bidirectional"))
    )
    (net (code "98") (name "unconnected-(SD-DAT2-Pad9)") (class "Default")
      (node (ref "SD") (pin "9") (pinfunction "DAT2_9") (pintype "bidirectional"))
    )
    (net (code "99") (name "unconnected-(SD-WRITE_PROTECT-PadWP)") (class "Default")
      (node (ref "SD") (pin "WP") (pinfunction "WRITE_PROTECT_WP") (pintype "passive"))
    )
    (net (code "100") (name "unconnected-(U$21-PA13{slash}I13{slash}I2C{slash}SERCOM2+4.1-Pad22)") (class "Default")
      (node (ref "U$21") (pin "22") (pinfunction "PA13/I13/I2C/SERCOM2+4.1_22") (pintype "bidirectional"))
    )
    (net (code "101") (name "unconnected-(U$21-PA27{slash}I15-Pad39)") (class "Default")
      (node (ref "U$21") (pin "39") (pinfunction "PA27/I15_39") (pintype "bidirectional"))
    )
    (net (code "102") (name "unconnected-(U$21-PA28{slash}I8-Pad41)") (class "Default")
      (node (ref "U$21") (pin "41") (pinfunction "PA28/I8_41") (pintype "bidirectional"))
    )
    (net (code "103") (name "unconnected-(U$21-PB22{slash}I6{slash}SERCOM5.2-Pad37)") (class "Default")
      (node (ref "U$21") (pin "37") (pinfunction "PB22/I6/SERCOM5.2_37") (pintype "bidirectional"))
    )
    (net (code "104") (name "unconnected-(U$21-PB23{slash}I7{slash}SERCOM5.3-Pad38)") (class "Default")
      (node (ref "U$21") (pin "38") (pinfunction "PB23/I7/SERCOM5.3_38") (pintype "bidirectional"))
    )
    (net (code "105") (name "unconnected-(U1-*RST-Pad4)") (class "Default")
      (node (ref "U1") (pin "4") (pinfunction "*RST_4") (pintype "passive"))
    )
    (net (code "106") (name "unconnected-(U1-32KHZ-Pad1)") (class "Default")
      (node (ref "U1") (pin "1") (pinfunction "32KHZ_1") (pintype "passive"))
    )
    (net (code "107") (name "unconnected-(U3-1PPS-PadP$37)") (class "Default")
      (node (ref "U3") (pin "P$37") (pinfunction "1PPS_P$37") (pintype "input"))
    )
    (net (code "108") (name "unconnected-(U3-ADC1-PadP$23)") (class "Default")
      (node (ref "U3") (pin "P$23") (pinfunction "ADC1_P$23") (pintype "input"))
    )
    (net (code "109") (name "unconnected-(U3-ADC2-PadP$24)") (class "Default")
      (node (ref "U3") (pin "P$24") (pinfunction "ADC2_P$24") (pintype "input"))
    )
    (net (code "110") (name "unconnected-(U3-ANT_BT-PadP$53)") (class "Default")
      (node (ref "U3") (pin "P$53") (pinfunction "ANT_BT_P$53") (pintype "bidirectional"))
    )
    (net (code "111") (name "unconnected-(U3-COL0-PadP$62)") (class "Default")
      (node (ref "U3") (pin "P$62") (pinfunction "COL0_P$62") (pintype "input"))
    )
    (net (code "112") (name "unconnected-(U3-COL1-PadP$61)") (class "Default")
      (node (ref "U3") (pin "P$61") (pinfunction "COL1_P$61") (pintype "input"))
    )
    (net (code "113") (name "unconnected-(U3-COL2-PadP$60)") (class "Default")
      (node (ref "U3") (pin "P$60") (pinfunction "COL2_P$60") (pintype "input"))
    )
    (net (code "114") (name "unconnected-(U3-COL3-PadP$59)") (class "Default")
      (node (ref "U3") (pin "P$59") (pinfunction "COL3_P$59") (pintype "input"))
    )
    (net (code "115") (name "unconnected-(U3-CTS-PadP$12)") (class "Default")
      (node (ref "U3") (pin "P$12") (pinfunction "CTS_P$12") (pintype "output"))
    )
    (net (code "116") (name "unconnected-(U3-DCD-PadP$11)") (class "Default")
      (node (ref "U3") (pin "P$11") (pinfunction "DCD_P$11") (pintype "output"))
    )
    (net (code "117") (name "unconnected-(U3-DTR-PadP$9)") (class "Default")
      (node (ref "U3") (pin "P$9") (pinfunction "DTR_P$9") (pintype "input"))
    )
    (net (code "118") (name "unconnected-(U3-GPIO5-PadP$43)") (class "Default")
      (node (ref "U3") (pin "P$43") (pinfunction "GPIO5_P$43") (pintype "bidirectional"))
    )
    (net (code "119") (name "unconnected-(U3-GPIO6-PadP$44)") (class "Default")
      (node (ref "U3") (pin "P$44") (pinfunction "GPIO6_P$44") (pintype "bidirectional"))
    )
    (net (code "120") (name "unconnected-(U3-MIC1N-PadP$20)") (class "Default")
      (node (ref "U3") (pin "P$20") (pinfunction "MIC1N_P$20") (pintype "input"))
    )
    (net (code "121") (name "unconnected-(U3-MIC1P-PadP$19)") (class "Default")
      (node (ref "U3") (pin "P$19") (pinfunction "MIC1P_P$19") (pintype "input"))
    )
    (net (code "122") (name "unconnected-(U3-PCM_CLK-PadP$46)") (class "Default")
      (node (ref "U3") (pin "P$46") (pinfunction "PCM_CLK_P$46") (pintype "input"))
    )
    (net (code "123") (name "unconnected-(U3-PCM_IN-PadP$47)") (class "Default")
      (node (ref "U3") (pin "P$47") (pinfunction "PCM_IN_P$47") (pintype "input"))
    )
    (net (code "124") (name "unconnected-(U3-PCM_OUT-PadP$48)") (class "Default")
      (node (ref "U3") (pin "P$48") (pinfunction "PCM_OUT_P$48") (pintype "output"))
    )
    (net (code "125") (name "unconnected-(U3-PCM_SYNC-PadP$45)") (class "Default")
      (node (ref "U3") (pin "P$45") (pinfunction "PCM_SYNC_P$45") (pintype "output"))
    )
    (net (code "126") (name "unconnected-(U3-PWM1-PadP$42)") (class "Default")
      (node (ref "U3") (pin "P$42") (pinfunction "PWM1_P$42") (pintype "output"))
    )
    (net (code "127") (name "unconnected-(U3-PWM2-PadP$41)") (class "Default")
      (node (ref "U3") (pin "P$41") (pinfunction "PWM2_P$41") (pintype "output"))
    )
    (net (code "128") (name "unconnected-(U3-RF_SYNC-PadP$63)") (class "Default")
      (node (ref "U3") (pin "P$63") (pinfunction "RF_SYNC_P$63") (pintype "output"))
    )
    (net (code "129") (name "unconnected-(U3-ROW0-PadP$58)") (class "Default")
      (node (ref "U3") (pin "P$58") (pinfunction "ROW0_P$58") (pintype "output"))
    )
    (net (code "130") (name "unconnected-(U3-ROW1-PadP$57)") (class "Default")
      (node (ref "U3") (pin "P$57") (pinfunction "ROW1_P$57") (pintype "output"))
    )
    (net (code "131") (name "unconnected-(U3-ROW2-PadP$56)") (class "Default")
      (node (ref "U3") (pin "P$56") (pinfunction "ROW2_P$56") (pintype "output"))
    )
    (net (code "132") (name "unconnected-(U3-ROW3-PadP$55)") (class "Default")
      (node (ref "U3") (pin "P$55") (pinfunction "ROW3_P$55") (pintype "output"))
    )
    (net (code "133") (name "unconnected-(U3-SCL-PadP$39)") (class "Default")
      (node (ref "U3") (pin "P$39") (pinfunction "SCL_P$39") (pintype "output"))
    )
    (net (code "134") (name "unconnected-(U3-SDA-PadP$38)") (class "Default")
      (node (ref "U3") (pin "P$38") (pinfunction "SDA_P$38") (pintype "bidirectional"))
    )
    (net (code "135") (name "unconnected-(U3-SIM_PRE-PadP$33)") (class "Default")
      (node (ref "U3") (pin "P$33") (pinfunction "SIM_PRE_P$33") (pintype "input"))
    )
    (net (code "136") (name "unconnected-(U3-SPK1N-PadP$22)") (class "Default")
      (node (ref "U3") (pin "P$22") (pinfunction "SPK1N_P$22") (pintype "output"))
    )
    (net (code "137") (name "unconnected-(U3-SPK1P-PadP$21)") (class "Default")
      (node (ref "U3") (pin "P$21") (pinfunction "SPK1P_P$21") (pintype "output"))
    )
    (net (code "138") (name "unconnected-(U3-USB_DM-PadP$27)") (class "Default")
      (node (ref "U3") (pin "P$27") (pinfunction "USB_DM_P$27") (pintype "bidirectional"))
    )
    (net (code "139") (name "unconnected-(U3-USB_DP-PadP$26)") (class "Default")
      (node (ref "U3") (pin "P$26") (pinfunction "USB_DP_P$26") (pintype "bidirectional"))
    )
    (net (code "140") (name "unconnected-(X8-5-PadC6)") (class "Default")
      (node (ref "X8") (pin "C6") (pinfunction "5_C6") (pintype "passive"))
    )
  )
)
